# uC_Main.net
KiCad netlist of a schematic drawn in EAGLE
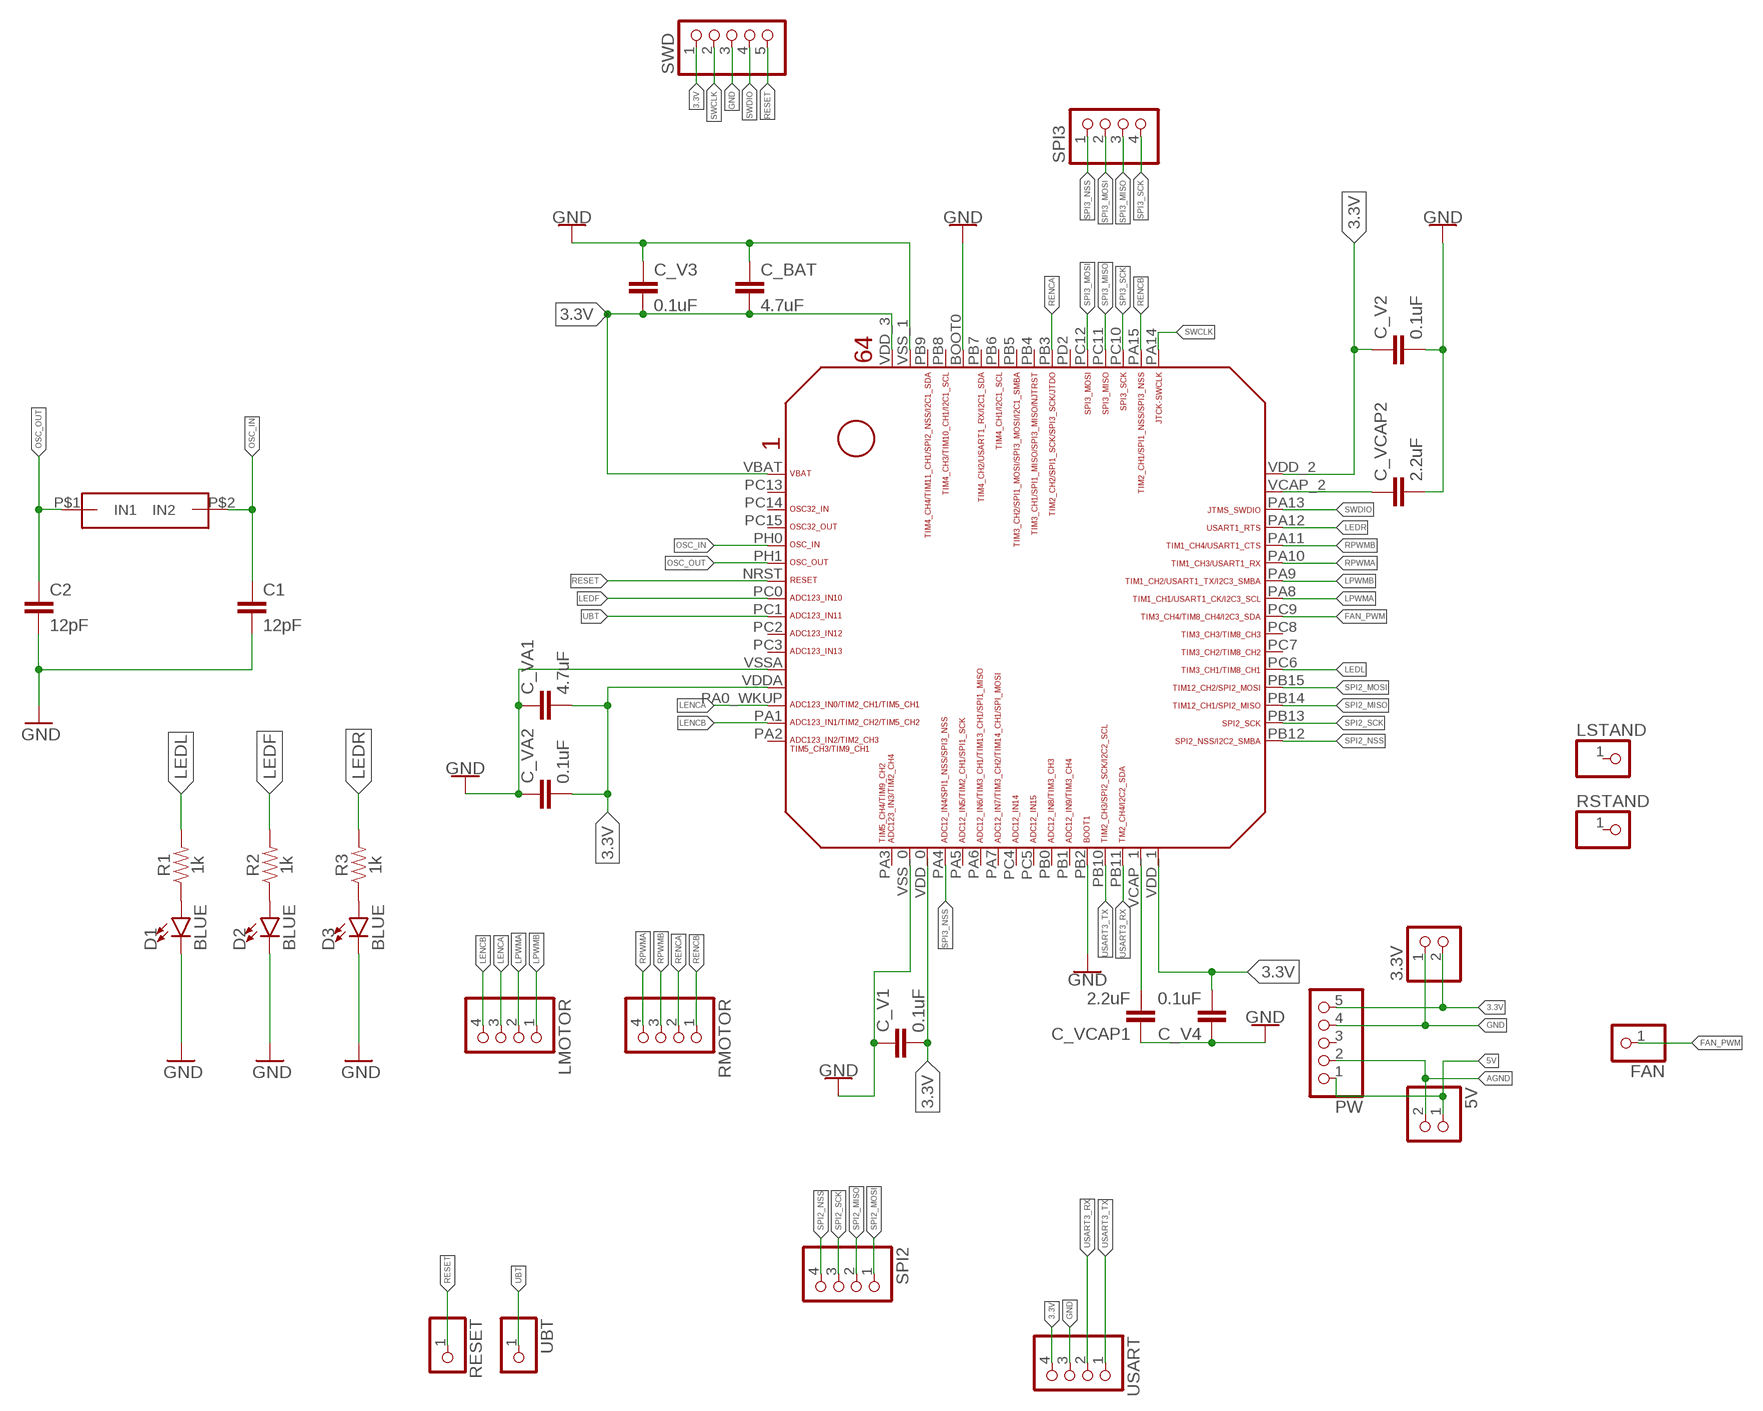
[diagram p0: schematic, sheet 1]

(export (version "E")
  (design (tool "Eeschema 10.0.6"))
  (components
    (comp (ref "3.3V")
      (value "PINHD-1X2")
      (footprint "eagle-import:1X02")
      (libsource (lib "eagle-import") (part "PINHD-1X2"))
    )
    (comp (ref "5V")
      (value "PINHD-1X2")
      (footprint "eagle-import:1X02")
      (libsource (lib "eagle-import") (part "PINHD-1X2"))
    )
    (comp (ref "C1")
      (value "12pF")
      (footprint "eagle-import:0603")
      (libsource (lib "eagle-import") (part "22PF-0603-50V-5%"))
    )
    (comp (ref "C2")
      (value "12pF")
      (footprint "eagle-import:0603")
      (libsource (lib "eagle-import") (part "22PF-0603-50V-5%"))
    )
    (comp (ref "C_BAT")
      (value "4.7uF")
      (footprint "eagle-import:0805")
      (libsource (lib "eagle-import") (part "22UF-0805-6.3V-20%"))
    )
    (comp (ref "C_V1")
      (value "0.1uF")
      (footprint "eagle-import:0805")
      (libsource (lib "eagle-import") (part "22UF-0805-6.3V-20%"))
    )
    (comp (ref "C_V2")
      (value "0.1uF")
      (footprint "eagle-import:0805")
      (libsource (lib "eagle-import") (part "22UF-0805-6.3V-20%"))
    )
    (comp (ref "C_V3")
      (value "0.1uF")
      (footprint "eagle-import:0805")
      (libsource (lib "eagle-import") (part "22UF-0805-6.3V-20%"))
    )
    (comp (ref "C_V4")
      (value "0.1uF")
      (footprint "eagle-import:0805")
      (libsource (lib "eagle-import") (part "22UF-0805-6.3V-20%"))
    )
    (comp (ref "C_VA1")
      (value "4.7uF")
      (footprint "eagle-import:0805")
      (libsource (lib "eagle-import") (part "22UF-0805-6.3V-20%"))
    )
    (comp (ref "C_VA2")
      (value "0.1uF")
      (footprint "eagle-import:0805")
      (libsource (lib "eagle-import") (part "22UF-0805-6.3V-20%"))
    )
    (comp (ref "C_VCAP1")
      (value "2.2uF")
      (footprint "eagle-import:0805")
      (libsource (lib "eagle-import") (part "22UF-0805-6.3V-20%"))
    )
    (comp (ref "C_VCAP2")
      (value "2.2uF")
      (footprint "eagle-import:0805")
      (libsource (lib "eagle-import") (part "22UF-0805-6.3V-20%"))
    )
    (comp (ref "D1")
      (value "BLUE")
      (footprint "eagle-import:LED-1206")
      (libsource (lib "eagle-import") (part "LED-BLUE1206"))
    )
    (comp (ref "D2")
      (value "BLUE")
      (footprint "eagle-import:LED-1206")
      (libsource (lib "eagle-import") (part "LED-BLUE1206"))
    )
    (comp (ref "D3")
      (value "BLUE")
      (footprint "eagle-import:LED-1206")
      (libsource (lib "eagle-import") (part "LED-BLUE1206"))
    )
    (comp (ref "FAN")
      (value "PINHD-1X1")
      (footprint "eagle-import:1X01")
      (libsource (lib "eagle-import") (part "PINHD-1X1"))
    )
    (comp (ref "LMOTOR")
      (value "PINHD-1X4")
      (footprint "eagle-import:1X04")
      (libsource (lib "eagle-import") (part "PINHD-1X4"))
    )
    (comp (ref "LSTAND")
      (value "PINHD-1X1")
      (footprint "eagle-import:1X01")
      (libsource (lib "eagle-import") (part "PINHD-1X1"))
    )
    (comp (ref "PW")
      (value "PINHD-1X5")
      (footprint "eagle-import:1X05")
      (libsource (lib "eagle-import") (part "PINHD-1X5"))
    )
    (comp (ref "R1")
      (value "1k")
      (footprint "eagle-import:0805")
      (libsource (lib "eagle-import") (part "0.75OHM-0805-1/4W-1%"))
    )
    (comp (ref "R2")
      (value "1k")
      (footprint "eagle-import:0805")
      (libsource (lib "eagle-import") (part "0.75OHM-0805-1/4W-1%"))
    )
    (comp (ref "R3")
      (value "1k")
      (footprint "eagle-import:0805")
      (libsource (lib "eagle-import") (part "0.75OHM-0805-1/4W-1%"))
    )
    (comp (ref "RESET")
      (value "PINHD-1X1")
      (footprint "eagle-import:1X01")
      (libsource (lib "eagle-import") (part "PINHD-1X1"))
    )
    (comp (ref "RMOTOR")
      (value "PINHD-1X4")
      (footprint "eagle-import:1X04")
      (libsource (lib "eagle-import") (part "PINHD-1X4"))
    )
    (comp (ref "RSTAND")
      (value "PINHD-1X1")
      (footprint "eagle-import:1X01")
      (libsource (lib "eagle-import") (part "PINHD-1X1"))
    )
    (comp (ref "SPI2")
      (value "PINHD-1X4")
      (footprint "eagle-import:1X04")
      (libsource (lib "eagle-import") (part "PINHD-1X4"))
    )
    (comp (ref "SPI3")
      (value "PINHD-1X4")
      (footprint "eagle-import:1X04")
      (libsource (lib "eagle-import") (part "PINHD-1X4"))
    )
    (comp (ref "SWD")
      (value "PINHD-1X5")
      (footprint "eagle-import:1X05")
      (libsource (lib "eagle-import") (part "PINHD-1X5"))
    )
    (comp (ref "U$1")
      (value "STM32F405/415_LQFP64")
      (footprint "eagle-import:STM32F405_415_LQFP64")
      (libsource (lib "eagle-import") (part "STM32F405/415_LQFP64"))
    )
    (comp (ref "U$2")
      (value "OSC")
      (footprint "eagle-import:OSC")
      (libsource (lib "eagle-import") (part "OSC"))
    )
    (comp (ref "UBT")
      (value "PINHD-1X1")
      (footprint "eagle-import:1X01")
      (libsource (lib "eagle-import") (part "PINHD-1X1"))
    )
    (comp (ref "USART")
      (value "PINHD-1X4")
      (footprint "eagle-import:1X04")
      (libsource (lib "eagle-import") (part "PINHD-1X4"))
    )
  )
  (nets
    (net (code "1") (name "3.3V") (class "Default")
      (node (ref "3.3V") (pin "2") (pinfunction "2_2") (pintype "passive"))
      (node (ref "C_BAT") (pin "2") (pinfunction "2_2") (pintype "passive"))
      (node (ref "C_V1") (pin "2") (pinfunction "2_2") (pintype "passive"))
      (node (ref "C_V2") (pin "1") (pinfunction "1_1") (pintype "passive"))
      (node (ref "C_V3") (pin "2") (pinfunction "2_2") (pintype "passive"))
      (node (ref "C_V4") (pin "2") (pinfunction "2_2") (pintype "passive"))
      (node (ref "C_VA1") (pin "2") (pinfunction "2_2") (pintype "passive"))
      (node (ref "C_VA2") (pin "2") (pinfunction "2_2") (pintype "passive"))
      (node (ref "PW") (pin "5") (pinfunction "5_5") (pintype "passive"))
      (node (ref "SWD") (pin "1") (pinfunction "1_1") (pintype "passive"))
      (node (ref "U$1") (pin "VBAT") (pinfunction "VBAT_VBAT") (pintype "bidirectional"))
      (node (ref "U$1") (pin "VDDA") (pinfunction "VDDA_VDDA") (pintype "bidirectional"))
      (node (ref "U$1") (pin "VDD_0") (pinfunction "VDD_0_VDD_0") (pintype "bidirectional"))
      (node (ref "U$1") (pin "VDD_1") (pinfunction "VDD_1_VDD_1") (pintype "bidirectional"))
      (node (ref "U$1") (pin "VDD_2") (pinfunction "VDD_2_VDD_2") (pintype "bidirectional"))
      (node (ref "U$1") (pin "VDD_3") (pinfunction "VDD_3_VDD_3") (pintype "bidirectional"))
      (node (ref "USART") (pin "4") (pinfunction "4_4") (pintype "passive"))
    )
    (net (code "2") (name "5V") (class "Default")
      (node (ref "5V") (pin "1") (pinfunction "1_1") (pintype "passive"))
      (node (ref "PW") (pin "1") (pinfunction "1_1") (pintype "passive"))
    )
    (net (code "3") (name "AGND") (class "Default")
      (node (ref "5V") (pin "2") (pinfunction "2_2") (pintype "passive"))
      (node (ref "PW") (pin "2") (pinfunction "2_2") (pintype "passive"))
    )
    (net (code "4") (name "FAN_PWM") (class "Default")
      (node (ref "FAN") (pin "1") (pinfunction "1_1") (pintype "passive"))
      (node (ref "U$1") (pin "PC9") (pinfunction "PC9_PC9") (pintype "bidirectional"))
    )
    (net (code "5") (name "GND") (class "Default")
      (node (ref "3.3V") (pin "1") (pinfunction "1_1") (pintype "passive"))
      (node (ref "C1") (pin "2") (pinfunction "2_2") (pintype "passive"))
      (node (ref "C2") (pin "2") (pinfunction "2_2") (pintype "passive"))
      (node (ref "C_BAT") (pin "1") (pinfunction "1_1") (pintype "passive"))
      (node (ref "C_V1") (pin "1") (pinfunction "1_1") (pintype "passive"))
      (node (ref "C_V2") (pin "2") (pinfunction "2_2") (pintype "passive"))
      (node (ref "C_V3") (pin "1") (pinfunction "1_1") (pintype "passive"))
      (node (ref "C_V4") (pin "1") (pinfunction "1_1") (pintype "passive"))
      (node (ref "C_VA1") (pin "1") (pinfunction "1_1") (pintype "passive"))
      (node (ref "C_VA2") (pin "1") (pinfunction "1_1") (pintype "passive"))
      (node (ref "C_VCAP1") (pin "1") (pinfunction "1_1") (pintype "passive"))
      (node (ref "C_VCAP2") (pin "2") (pinfunction "2_2") (pintype "passive"))
      (node (ref "D1") (pin "C") (pinfunction "C_C") (pintype "passive"))
      (node (ref "D2") (pin "C") (pinfunction "C_C") (pintype "passive"))
      (node (ref "D3") (pin "C") (pinfunction "C_C") (pintype "passive"))
      (node (ref "PW") (pin "4") (pinfunction "4_4") (pintype "passive"))
      (node (ref "SWD") (pin "3") (pinfunction "3_3") (pintype "passive"))
      (node (ref "U$1") (pin "BOOT0") (pinfunction "BOOT0_BOOT0") (pintype "bidirectional"))
      (node (ref "U$1") (pin "PB2") (pinfunction "PB2_PB2") (pintype "bidirectional"))
      (node (ref "U$1") (pin "VSSA") (pinfunction "VSSA_VSSA") (pintype "bidirectional"))
      (node (ref "U$1") (pin "VSS_0") (pinfunction "VSS_0_VSS_0") (pintype "bidirectional"))
      (node (ref "U$1") (pin "VSS_1") (pinfunction "VSS_1_VSS_1") (pintype "bidirectional"))
      (node (ref "USART") (pin "3") (pinfunction "3_3") (pintype "passive"))
    )
    (net (code "6") (name "LEDF") (class "Default")
      (node (ref "R2") (pin "2") (pinfunction "2_2") (pintype "passive"))
      (node (ref "U$1") (pin "PC0") (pinfunction "PC0_PC0") (pintype "bidirectional"))
    )
    (net (code "7") (name "LEDL") (class "Default")
      (node (ref "R1") (pin "2") (pinfunction "2_2") (pintype "passive"))
      (node (ref "U$1") (pin "PC6") (pinfunction "PC6_PC6") (pintype "bidirectional"))
    )
    (net (code "8") (name "LEDR") (class "Default")
      (node (ref "R3") (pin "2") (pinfunction "2_2") (pintype "passive"))
      (node (ref "U$1") (pin "PA12") (pinfunction "PA12_PA12") (pintype "bidirectional"))
    )
    (net (code "9") (name "LENCA") (class "Default")
      (node (ref "LMOTOR") (pin "3") (pinfunction "3_3") (pintype "passive"))
      (node (ref "U$1") (pin "PA0_WKUP") (pinfunction "PA0_AKUP_PA0_WKUP") (pintype "bidirectional"))
    )
    (net (code "10") (name "LENCB") (class "Default")
      (node (ref "LMOTOR") (pin "4") (pinfunction "4_4") (pintype "passive"))
      (node (ref "U$1") (pin "PA1") (pinfunction "PA1_PA1") (pintype "bidirectional"))
    )
    (net (code "11") (name "LPWMA") (class "Default")
      (node (ref "LMOTOR") (pin "2") (pinfunction "2_2") (pintype "passive"))
      (node (ref "U$1") (pin "PA8") (pinfunction "PA8_PA8") (pintype "bidirectional"))
    )
    (net (code "12") (name "LPWMB") (class "Default")
      (node (ref "LMOTOR") (pin "1") (pinfunction "1_1") (pintype "passive"))
      (node (ref "U$1") (pin "PA9") (pinfunction "PA9_PA9") (pintype "bidirectional"))
    )
    (net (code "13") (name "Net-(C_VCAP1-Pad2)") (class "Default")
      (node (ref "C_VCAP1") (pin "2") (pinfunction "2_2") (pintype "passive"))
      (node (ref "U$1") (pin "VCAP_1") (pinfunction "VCAP_1_VCAP_1") (pintype "bidirectional"))
    )
    (net (code "14") (name "Net-(C_VCAP2-Pad1)") (class "Default")
      (node (ref "C_VCAP2") (pin "1") (pinfunction "1_1") (pintype "passive"))
      (node (ref "U$1") (pin "VCAP_2") (pinfunction "VCAP_2_VCAP_2") (pintype "bidirectional"))
    )
    (net (code "15") (name "Net-(D1-PadA)") (class "Default")
      (node (ref "D1") (pin "A") (pinfunction "A_A") (pintype "passive"))
      (node (ref "R1") (pin "1") (pinfunction "1_1") (pintype "passive"))
    )
    (net (code "16") (name "Net-(D2-PadA)") (class "Default")
      (node (ref "D2") (pin "A") (pinfunction "A_A") (pintype "passive"))
      (node (ref "R2") (pin "1") (pinfunction "1_1") (pintype "passive"))
    )
    (net (code "17") (name "Net-(D3-PadA)") (class "Default")
      (node (ref "D3") (pin "A") (pinfunction "A_A") (pintype "passive"))
      (node (ref "R3") (pin "1") (pinfunction "1_1") (pintype "passive"))
    )
    (net (code "18") (name "OSC_IN") (class "Default")
      (node (ref "C1") (pin "1") (pinfunction "1_1") (pintype "passive"))
      (node (ref "U$1") (pin "PH0") (pinfunction "PH0_PH0") (pintype "bidirectional"))
      (node (ref "U$2") (pin "P$2") (pinfunction "IN2_P$2") (pintype "bidirectional"))
    )
    (net (code "19") (name "OSC_OUT") (class "Default")
      (node (ref "C2") (pin "1") (pinfunction "1_1") (pintype "passive"))
      (node (ref "U$1") (pin "PH1") (pinfunction "PH1_PH1") (pintype "bidirectional"))
      (node (ref "U$2") (pin "P$1") (pinfunction "IN1_P$1") (pintype "bidirectional"))
    )
    (net (code "20") (name "RENCA") (class "Default")
      (node (ref "RMOTOR") (pin "2") (pinfunction "2_2") (pintype "passive"))
      (node (ref "U$1") (pin "PB3") (pinfunction "PB3_PB3") (pintype "bidirectional"))
    )
    (net (code "21") (name "RENCB") (class "Default")
      (node (ref "RMOTOR") (pin "1") (pinfunction "1_1") (pintype "passive"))
      (node (ref "U$1") (pin "PA15") (pinfunction "PA15_PA15") (pintype "bidirectional"))
    )
    (net (code "22") (name "RESET") (class "Default")
      (node (ref "RESET") (pin "1") (pinfunction "1_1") (pintype "passive"))
      (node (ref "SWD") (pin "5") (pinfunction "5_5") (pintype "passive"))
      (node (ref "U$1") (pin "NRST") (pinfunction "NRST_NRST") (pintype "bidirectional"))
    )
    (net (code "23") (name "RPWMA") (class "Default")
      (node (ref "RMOTOR") (pin "4") (pinfunction "4_4") (pintype "passive"))
      (node (ref "U$1") (pin "PA10") (pinfunction "PA10_PA10") (pintype "bidirectional"))
    )
    (net (code "24") (name "RPWMB") (class "Default")
      (node (ref "RMOTOR") (pin "3") (pinfunction "3_3") (pintype "passive"))
      (node (ref "U$1") (pin "PA11") (pinfunction "PA11_PA11") (pintype "bidirectional"))
    )
    (net (code "25") (name "SPI2_MISO") (class "Default")
      (node (ref "SPI2") (pin "2") (pinfunction "2_2") (pintype "passive"))
      (node (ref "U$1") (pin "PB14") (pinfunction "PB14_PB14") (pintype "bidirectional"))
    )
    (net (code "26") (name "SPI2_MOSI") (class "Default")
      (node (ref "SPI2") (pin "1") (pinfunction "1_1") (pintype "passive"))
      (node (ref "U$1") (pin "PB15") (pinfunction "PB15_PB15") (pintype "bidirectional"))
    )
    (net (code "27") (name "SPI2_NSS") (class "Default")
      (node (ref "SPI2") (pin "4") (pinfunction "4_4") (pintype "passive"))
      (node (ref "U$1") (pin "PB12") (pinfunction "PB12_PB12") (pintype "bidirectional"))
    )
    (net (code "28") (name "SPI2_SCK") (class "Default")
      (node (ref "SPI2") (pin "3") (pinfunction "3_3") (pintype "passive"))
      (node (ref "U$1") (pin "PB13") (pinfunction "PB13_PB13") (pintype "bidirectional"))
    )
    (net (code "29") (name "SPI3_MISO") (class "Default")
      (node (ref "SPI3") (pin "3") (pinfunction "3_3") (pintype "passive"))
      (node (ref "U$1") (pin "PC11") (pinfunction "PC11_PC11") (pintype "bidirectional"))
    )
    (net (code "30") (name "SPI3_MOSI") (class "Default")
      (node (ref "SPI3") (pin "2") (pinfunction "2_2") (pintype "passive"))
      (node (ref "U$1") (pin "PC12") (pinfunction "PC12_PC12") (pintype "bidirectional"))
    )
    (net (code "31") (name "SPI3_NSS") (class "Default")
      (node (ref "SPI3") (pin "1") (pinfunction "1_1") (pintype "passive"))
      (node (ref "U$1") (pin "PA4") (pinfunction "PA4_PA4") (pintype "bidirectional"))
    )
    (net (code "32") (name "SPI3_SCK") (class "Default")
      (node (ref "SPI3") (pin "4") (pinfunction "4_4") (pintype "passive"))
      (node (ref "U$1") (pin "PC10") (pinfunction "PC10_PC10") (pintype "bidirectional"))
    )
    (net (code "33") (name "SWCLK") (class "Default")
      (node (ref "SWD") (pin "2") (pinfunction "2_2") (pintype "passive"))
      (node (ref "U$1") (pin "PA14") (pinfunction "PA14_PA14") (pintype "bidirectional"))
    )
    (net (code "34") (name "SWDIO") (class "Default")
      (node (ref "SWD") (pin "4") (pinfunction "4_4") (pintype "passive"))
      (node (ref "U$1") (pin "PA13") (pinfunction "PA13_PA13") (pintype "bidirectional"))
    )
    (net (code "35") (name "UBT") (class "Default")
      (node (ref "U$1") (pin "PC1") (pinfunction "PC1_PC1") (pintype "bidirectional"))
      (node (ref "UBT") (pin "1") (pinfunction "1_1") (pintype "passive"))
    )
    (net (code "36") (name "USART3_RX") (class "Default")
      (node (ref "U$1") (pin "PB11") (pinfunction "PB11_PB11") (pintype "bidirectional"))
      (node (ref "USART") (pin "2") (pinfunction "2_2") (pintype "passive"))
    )
    (net (code "37") (name "USART3_TX") (class "Default")
      (node (ref "U$1") (pin "PB10") (pinfunction "PB10_PB10") (pintype "bidirectional"))
      (node (ref "USART") (pin "1") (pinfunction "1_1") (pintype "passive"))
    )
    (net (code "38") (name "unconnected-(LSTAND-Pad1)") (class "Default")
      (node (ref "LSTAND") (pin "1") (pinfunction "1_1") (pintype "passive"))
    )
    (net (code "39") (name "unconnected-(PW-Pad3)") (class "Default")
      (node (ref "PW") (pin "3") (pinfunction "3_3") (pintype "passive"))
    )
    (net (code "40") (name "unconnected-(RSTAND-Pad1)") (class "Default")
      (node (ref "RSTAND") (pin "1") (pinfunction "1_1") (pintype "passive"))
    )
    (net (code "41") (name "unconnected-(U$1-PadPA2)") (class "Default")
      (node (ref "U$1") (pin "PA2") (pinfunction "PA2_PA2") (pintype "bidirectional"))
    )
    (net (code "42") (name "unconnected-(U$1-PadPA3)") (class "Default")
      (node (ref "U$1") (pin "PA3") (pinfunction "PA3_PA3") (pintype "bidirectional"))
    )
    (net (code "43") (name "unconnected-(U$1-PadPA5)") (class "Default")
      (node (ref "U$1") (pin "PA5") (pinfunction "PA5_PA5") (pintype "bidirectional"))
    )
    (net (code "44") (name "unconnected-(U$1-PadPA6)") (class "Default")
      (node (ref "U$1") (pin "PA6") (pinfunction "PA6_PA6") (pintype "bidirectional"))
    )
    (net (code "45") (name "unconnected-(U$1-PadPA7)") (class "Default")
      (node (ref "U$1") (pin "PA7") (pinfunction "PA7_PA7") (pintype "bidirectional"))
    )
    (net (code "46") (name "unconnected-(U$1-PadPB0)") (class "Default")
      (node (ref "U$1") (pin "PB0") (pinfunction "PB0_PB0") (pintype "bidirectional"))
    )
    (net (code "47") (name "unconnected-(U$1-PadPB1)") (class "Default")
      (node (ref "U$1") (pin "PB1") (pinfunction "PB1_PB1") (pintype "bidirectional"))
    )
    (net (code "48") (name "unconnected-(U$1-PadPB4)") (class "Default")
      (node (ref "U$1") (pin "PB4") (pinfunction "PB4_PB4") (pintype "bidirectional"))
    )
    (net (code "49") (name "unconnected-(U$1-PadPB5)") (class "Default")
      (node (ref "U$1") (pin "PB5") (pinfunction "PB5_PB5") (pintype "bidirectional"))
    )
    (net (code "50") (name "unconnected-(U$1-PadPB6)") (class "Default")
      (node (ref "U$1") (pin "PB6") (pinfunction "PB6_PB6") (pintype "bidirectional"))
    )
    (net (code "51") (name "unconnected-(U$1-PadPB7)") (class "Default")
      (node (ref "U$1") (pin "PB7") (pinfunction "PB7_PB7") (pintype "bidirectional"))
    )
    (net (code "52") (name "unconnected-(U$1-PadPB8)") (class "Default")
      (node (ref "U$1") (pin "PB8") (pinfunction "PB8_PB8") (pintype "bidirectional"))
    )
    (net (code "53") (name "unconnected-(U$1-PadPB9)") (class "Default")
      (node (ref "U$1") (pin "PB9") (pinfunction "PB9_PB9") (pintype "bidirectional"))
    )
    (net (code "54") (name "unconnected-(U$1-PadPC2)") (class "Default")
      (node (ref "U$1") (pin "PC2") (pinfunction "PC2_PC2") (pintype "bidirectional"))
    )
    (net (code "55") (name "unconnected-(U$1-PadPC3)") (class "Default")
      (node (ref "U$1") (pin "PC3") (pinfunction "PC3_PC3") (pintype "bidirectional"))
    )
    (net (code "56") (name "unconnected-(U$1-PadPC4)") (class "Default")
      (node (ref "U$1") (pin "PC4") (pinfunction "PC4_PC4") (pintype "bidirectional"))
    )
    (net (code "57") (name "unconnected-(U$1-PadPC5)") (class "Default")
      (node (ref "U$1") (pin "PC5") (pinfunction "PC5_PC5") (pintype "bidirectional"))
    )
    (net (code "58") (name "unconnected-(U$1-PadPC7)") (class "Default")
      (node (ref "U$1") (pin "PC7") (pinfunction "PC7_PC7") (pintype "bidirectional"))
    )
    (net (code "59") (name "unconnected-(U$1-PadPC8)") (class "Default")
      (node (ref "U$1") (pin "PC8") (pinfunction "PC8_PC8") (pintype "bidirectional"))
    )
    (net (code "60") (name "unconnected-(U$1-PadPC13)") (class "Default")
      (node (ref "U$1") (pin "PC13") (pinfunction "PC13_PC13") (pintype "bidirectional"))
    )
    (net (code "61") (name "unconnected-(U$1-PadPC14)") (class "Default")
      (node (ref "U$1") (pin "PC14") (pinfunction "PC14_PC14") (pintype "bidirectional"))
    )
    (net (code "62") (name "unconnected-(U$1-PadPC15)") (class "Default")
      (node (ref "U$1") (pin "PC15") (pinfunction "PC15_PC15") (pintype "bidirectional"))
    )
    (net (code "63") (name "unconnected-(U$1-PadPD2)") (class "Default")
      (node (ref "U$1") (pin "PD2") (pinfunction "PD2_PD2") (pintype "bidirectional"))
    )
  )
)
